# 2V5_DRS4_SUPPLY.net
KiCad netlist of a schematic drawn in Altium Designer
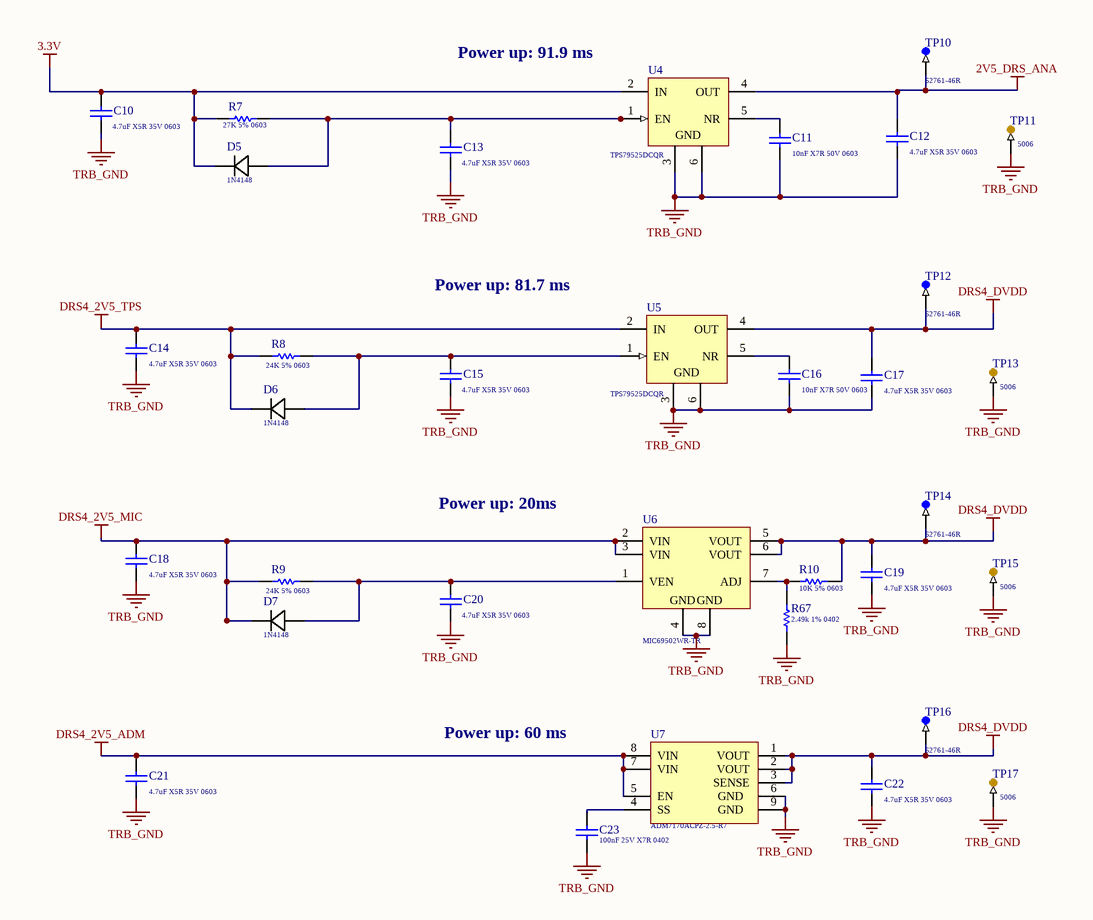
[diagram p0: 2V5_DRS4_SUPPLY.SchDoc]

(export (version "E")
  (design (tool "Eeschema 10.0.6"))
  (components
    (comp (ref "C10")
      (value "Cap_Murata_ZRB18AR6YA475ME05L_4.7uF")
      (footprint "Cap_Murata_ZRB18AR6YA475ME05L_4.7uF")
      (description "CAP CER 4.7uF 35V X5R 0603")
      (fields (field (name "CAPACITANCE") "4.7uF X5R 35V 0603"))
      (libsource (lib "Cap_Murata_ZRB18AR6YA475ME05L_4.7uF") (part "Cap_Murata_ZRB18AR6YA475ME05L_4.7uF"))
    )
    (comp (ref "C11")
      (value "Cap_Kemet_C0603C103J5RACTU_eec")
      (footprint "Kemet_C0603_0")
      (description "CAP CER 10nF 50V X7R 0603")
      (fields
        (field (name "PART NUMBER") "C0603C103J5RACTU")
        (field (name "MANUFACTURER") "Kemet")
        (field (name "CAPACITANCE") "10nF X7R 50V 0603")
      )
      (libsource (lib "Cap_Kemet_C0603C103J5RACTU_10nF") (part "Cap_Kemet_C0603C103J5RACTU_eec"))
    )
    (comp (ref "C12")
      (value "Cap_Murata_ZRB18AR6YA475ME05L_4.7uF")
      (footprint "Cap_Murata_ZRB18AR6YA475ME05L_4.7uF")
      (description "CAP CER 4.7uF 35V X5R 0603")
      (fields (field (name "CAPACITANCE") "4.7uF X5R 35V 0603"))
      (libsource (lib "Cap_Murata_ZRB18AR6YA475ME05L_4.7uF") (part "Cap_Murata_ZRB18AR6YA475ME05L_4.7uF"))
    )
    (comp (ref "C13")
      (value "Cap_Murata_ZRB18AR6YA475ME05L_4.7uF")
      (footprint "Cap_Murata_ZRB18AR6YA475ME05L_4.7uF")
      (description "CAP CER 4.7uF 35V X5R 0603")
      (fields (field (name "CAPACITANCE") "4.7uF X5R 35V 0603"))
      (libsource (lib "Cap_Murata_ZRB18AR6YA475ME05L_4.7uF") (part "Cap_Murata_ZRB18AR6YA475ME05L_4.7uF"))
    )
    (comp (ref "C14")
      (value "Cap_Murata_ZRB18AR6YA475ME05L_4.7uF")
      (footprint "Cap_Murata_ZRB18AR6YA475ME05L_4.7uF")
      (description "CAP CER 4.7uF 35V X5R 0603")
      (fields (field (name "CAPACITANCE") "4.7uF X5R 35V 0603"))
      (libsource (lib "Cap_Murata_ZRB18AR6YA475ME05L_4.7uF") (part "Cap_Murata_ZRB18AR6YA475ME05L_4.7uF"))
    )
    (comp (ref "C15")
      (value "Cap_Murata_ZRB18AR6YA475ME05L_4.7uF")
      (footprint "Cap_Murata_ZRB18AR6YA475ME05L_4.7uF")
      (description "CAP CER 4.7uF 35V X5R 0603")
      (fields (field (name "CAPACITANCE") "4.7uF X5R 35V 0603"))
      (libsource (lib "Cap_Murata_ZRB18AR6YA475ME05L_4.7uF") (part "Cap_Murata_ZRB18AR6YA475ME05L_4.7uF"))
    )
    (comp (ref "C16")
      (value "Cap_Kemet_C0603C103J5RACTU_eec")
      (footprint "Kemet_C0603_0")
      (description "CAP CER 10nF 50V X7R 0603")
      (fields
        (field (name "PART NUMBER") "C0603C103J5RACTU")
        (field (name "MANUFACTURER") "Kemet")
        (field (name "CAPACITANCE") "10nF X7R 50V 0603")
      )
      (libsource (lib "Cap_Kemet_C0603C103J5RACTU_10nF") (part "Cap_Kemet_C0603C103J5RACTU_eec"))
    )
    (comp (ref "C17")
      (value "Cap_Murata_ZRB18AR6YA475ME05L_4.7uF")
      (footprint "Cap_Murata_ZRB18AR6YA475ME05L_4.7uF")
      (description "CAP CER 4.7uF 35V X5R 0603")
      (fields (field (name "CAPACITANCE") "4.7uF X5R 35V 0603"))
      (libsource (lib "Cap_Murata_ZRB18AR6YA475ME05L_4.7uF") (part "Cap_Murata_ZRB18AR6YA475ME05L_4.7uF"))
    )
    (comp (ref "C18")
      (value "Cap_Murata_ZRB18AR6YA475ME05L_4.7uF")
      (footprint "Cap_Murata_ZRB18AR6YA475ME05L_4.7uF")
      (description "CAP CER 4.7uF 35V X5R 0603")
      (fields (field (name "CAPACITANCE") "4.7uF X5R 35V 0603"))
      (libsource (lib "Cap_Murata_ZRB18AR6YA475ME05L_4.7uF") (part "Cap_Murata_ZRB18AR6YA475ME05L_4.7uF"))
    )
    (comp (ref "C19")
      (value "Cap_Murata_ZRB18AR6YA475ME05L_4.7uF")
      (footprint "Cap_Murata_ZRB18AR6YA475ME05L_4.7uF")
      (description "CAP CER 4.7uF 35V X5R 0603")
      (fields (field (name "CAPACITANCE") "4.7uF X5R 35V 0603"))
      (libsource (lib "Cap_Murata_ZRB18AR6YA475ME05L_4.7uF") (part "Cap_Murata_ZRB18AR6YA475ME05L_4.7uF"))
    )
    (comp (ref "C20")
      (value "Cap_Murata_ZRB18AR6YA475ME05L_4.7uF")
      (footprint "Cap_Murata_ZRB18AR6YA475ME05L_4.7uF")
      (description "CAP CER 4.7uF 35V X5R 0603")
      (fields (field (name "CAPACITANCE") "4.7uF X5R 35V 0603"))
      (libsource (lib "Cap_Murata_ZRB18AR6YA475ME05L_4.7uF") (part "Cap_Murata_ZRB18AR6YA475ME05L_4.7uF"))
    )
    (comp (ref "C21")
      (value "Cap_Murata_ZRB18AR6YA475ME05L_4.7uF")
      (footprint "Cap_Murata_ZRB18AR6YA475ME05L_4.7uF")
      (description "CAP CER 4.7uF 35V X5R 0603")
      (fields (field (name "CAPACITANCE") "4.7uF X5R 35V 0603"))
      (libsource (lib "Cap_Murata_ZRB18AR6YA475ME05L_4.7uF") (part "Cap_Murata_ZRB18AR6YA475ME05L_4.7uF"))
    )
    (comp (ref "C22")
      (value "Cap_Murata_ZRB18AR6YA475ME05L_4.7uF")
      (footprint "Cap_Murata_ZRB18AR6YA475ME05L_4.7uF")
      (description "CAP CER 4.7uF 35V X5R 0603")
      (fields (field (name "CAPACITANCE") "4.7uF X5R 35V 0603"))
      (libsource (lib "Cap_Murata_ZRB18AR6YA475ME05L_4.7uF") (part "Cap_Murata_ZRB18AR6YA475ME05L_4.7uF"))
    )
    (comp (ref "C23")
      (value "Cap_Taiyo_Yuden_TMK105B7104KV-FR_100nF")
      (footprint "Cap_Taiyo_Yuden_TMK105B7104KV-FR_100nF")
      (description "CAP CER 100nF 25V X7R 0402")
      (fields (field (name "CAPACITANCE") "100nF 25V X7R 0402"))
      (libsource (lib "Cap_Taiyo_Yuden_TMK105B7104KV-FR_100nF") (part "Cap_Taiyo_Yuden_TMK105B7104KV-FR_100nF"))
    )
    (comp (ref "D5")
      (value "Diode_ON_Semiconductor_1N4148WT_300mA")
      (footprint "Diode_ON_Semiconductor_1N4148WT_300mA")
      (description "Diodes - General Purpose, Power, Switching SINGLE JUNC. 75V 4.0NS COMP")
      (fields (field (name "SERIES") "1N4148"))
      (libsource (lib "Diode_ON_Semiconductor_1N4148WT_300mA") (part "Diode_ON_Semiconductor_1N4148WT_300mA"))
    )
    (comp (ref "D6")
      (value "Diode_ON_Semiconductor_1N4148WT_300mA")
      (footprint "Diode_ON_Semiconductor_1N4148WT_300mA")
      (description "Diodes - General Purpose, Power, Switching SINGLE JUNC. 75V 4.0NS COMP")
      (fields (field (name "SERIES") "1N4148"))
      (libsource (lib "Diode_ON_Semiconductor_1N4148WT_300mA") (part "Diode_ON_Semiconductor_1N4148WT_300mA"))
    )
    (comp (ref "D7")
      (value "Diode_ON_Semiconductor_1N4148WT_300mA")
      (footprint "Diode_ON_Semiconductor_1N4148WT_300mA")
      (description "Diodes - General Purpose, Power, Switching SINGLE JUNC. 75V 4.0NS COMP")
      (fields (field (name "SERIES") "1N4148"))
      (libsource (lib "Diode_ON_Semiconductor_1N4148WT_300mA") (part "Diode_ON_Semiconductor_1N4148WT_300mA"))
    )
    (comp (ref "R7")
      (value "27K 5% 0603")
      (footprint "RESC0603(1608)_L")
      (description "27K 0.1W 5% 0603 (1608 Metric)  SMD")
      (fields (field (name "POWER") "0.1 W") (field (name "TOLERANCE") "5 %"))
      (libsource (lib "Altium Content Vault") (part "RES"))
    )
    (comp (ref "R8")
      (value "24K 5% 0603")
      (footprint "RESC0603(1608)_L")
      (description "24K 0.1W 5% 0603 (1608 Metric)  SMD")
      (fields (field (name "TOLERANCE") "5 %") (field (name "POWER") "0.1 W"))
      (libsource (lib "Altium Content Vault") (part "RES"))
    )
    (comp (ref "R9")
      (value "24K 5% 0603")
      (footprint "RESC0603(1608)_L")
      (description "24K 0.1W 5% 0603 (1608 Metric)  SMD")
      (fields (field (name "TOLERANCE") "5 %") (field (name "POWER") "0.1 W"))
      (libsource (lib "Altium Content Vault") (part "RES"))
    )
    (comp (ref "R10")
      (value "10K 5% 0603")
      (footprint "RESC0603(1608)_L")
      (description "10K 0.1W 5% 0603 (1608 Metric)  SMD")
      (fields (field (name "TOLERANCE") "5 %") (field (name "POWER") "0.1 W"))
      (libsource (lib "Altium Content Vault") (part "RES"))
    )
    (comp (ref "R67")
      (value "Res_Yageo_RC0402FR-132K49L_2.48kOhm")
      (footprint "Res_Yageo_RC0402FR-132K49L_2.48kOhm")
      (description "Thick Film Resistors - SMD 2.49K ohm 1% 50V General Purpose")
      (fields (field (name "RESISTANCE") "2.49k 1% 0402"))
      (libsource (lib "Res_Yageo_RC0402FR-132K49L_2.48kOhm") (part "Res_Yageo_RC0402FR-132K49L_2.48kOhm"))
    )
    (comp (ref "TP10")
      (value "TP_Harwin_S2761_46R")
      (footprint "TP_Harwin_S2761_46R")
      (description "Circuit Board Hardware - PCB SMT Mini Test Terminal, Reel")
      (fields (field (name "SERIES") "S2761-46R"))
      (libsource (lib "TP_Harwin_S2761_46R") (part "TP_Harwin_S2761_46R"))
    )
    (comp (ref "TP11")
      (value "TP_Keystone_Electronics_5006")
      (footprint "TP_Keystone_Electronics_5006")
      (description "Circuit Board Hardware - PCB TEST POINT BLK .063")
      (fields (field (name "SERIES") "5006"))
      (libsource (lib "TP_Keystone_Electronics_5006") (part "TP_Keystone_Electronics_5006"))
    )
    (comp (ref "TP12")
      (value "TP_Harwin_S2761_46R")
      (footprint "TP_Harwin_S2761_46R")
      (description "Circuit Board Hardware - PCB SMT Mini Test Terminal, Reel")
      (fields (field (name "SERIES") "S2761-46R"))
      (libsource (lib "TP_Harwin_S2761_46R") (part "TP_Harwin_S2761_46R"))
    )
    (comp (ref "TP13")
      (value "TP_Keystone_Electronics_5006")
      (footprint "TP_Keystone_Electronics_5006")
      (description "Circuit Board Hardware - PCB TEST POINT BLK .063")
      (fields (field (name "SERIES") "5006"))
      (libsource (lib "TP_Keystone_Electronics_5006") (part "TP_Keystone_Electronics_5006"))
    )
    (comp (ref "TP14")
      (value "TP_Harwin_S2761_46R")
      (footprint "TP_Harwin_S2761_46R")
      (description "Circuit Board Hardware - PCB SMT Mini Test Terminal, Reel")
      (fields (field (name "SERIES") "S2761-46R"))
      (libsource (lib "TP_Harwin_S2761_46R") (part "TP_Harwin_S2761_46R"))
    )
    (comp (ref "TP15")
      (value "TP_Keystone_Electronics_5006")
      (footprint "TP_Keystone_Electronics_5006")
      (description "Circuit Board Hardware - PCB TEST POINT BLK .063")
      (fields (field (name "SERIES") "5006"))
      (libsource (lib "TP_Keystone_Electronics_5006") (part "TP_Keystone_Electronics_5006"))
    )
    (comp (ref "TP16")
      (value "TP_Harwin_S2761_46R")
      (footprint "TP_Harwin_S2761_46R")
      (description "Circuit Board Hardware - PCB SMT Mini Test Terminal, Reel")
      (fields (field (name "SERIES") "S2761-46R"))
      (libsource (lib "TP_Harwin_S2761_46R") (part "TP_Harwin_S2761_46R"))
    )
    (comp (ref "TP17")
      (value "TP_Keystone_Electronics_5006")
      (footprint "TP_Keystone_Electronics_5006")
      (description "Circuit Board Hardware - PCB TEST POINT BLK .063")
      (fields (field (name "SERIES") "5006"))
      (libsource (lib "TP_Keystone_Electronics_5006") (part "TP_Keystone_Electronics_5006"))
    )
    (comp (ref "U4")
      (value "TPS79525DCQR")
      (footprint "DCQ0006A_N")
      (fields (field (name "MANUFACTURER") "Texas Instruments"))
      (libsource (lib "IC_Texas Instruments_TPS79525DCQR") (part "TPS79525DCQR"))
    )
    (comp (ref "U5")
      (value "TPS79525DCQR")
      (footprint "DCQ0006A_N")
      (fields (field (name "MANUFACTURER") "Texas Instruments"))
      (libsource (lib "IC_Texas Instruments_TPS79525DCQR") (part "TPS79525DCQR"))
    )
    (comp (ref "U6")
      (value "LDO_Microchip_MIC69502WR-TR_ADJ")
      (footprint "LDO_Microchip_MIC69502WR-TR_ADJ")
      (description "LDO Voltage Regulators 5A Low VIN LDO Regulator with 0.5Vref")
      (fields (field (name "SERIES") "MIC69502WR-TR"))
      (libsource (lib "LDO_Microchip_MIC69502WR-TR_ADJ") (part "LDO_Microchip_MIC69502WR-TR_ADJ"))
    )
    (comp (ref "U7")
      (value "LDO_Analog_Devices_ADM7170ACPZ-2.5-R7_2.5V")
      (footprint "LDO_Analog_Devices_ADM7170ACPZ-2.5-R7_2.5V")
      (description "LDO Voltage Regulators 0.5A Hi PSRR FT LDO 2.5V")
      (fields (field (name "SERIES") "ADM7170ACPZ-2.5-R7"))
      (libsource (lib "LDO_Analog_Devices_ADM7170ACPZ-2.5-R7_2.5V") (part "LDO_Analog_Devices_ADM7170ACPZ-2.5-R7_2.5V"))
    )
  )
  (nets
    (net (code "1") (name "2V5_DRS_ANA") (class "Default")
      (node (ref "C12") (pin "2") (pinfunction "2_2") (pintype "passive"))
      (node (ref "TP10") (pin "1") (pinfunction "1_1") (pintype "input"))
      (node (ref "U4") (pin "4") (pinfunction "OUT_4") (pintype "power_in"))
    )
    (net (code "2") (name "3.3V") (class "Default")
      (node (ref "C10") (pin "2") (pinfunction "2_2") (pintype "passive"))
      (node (ref "D5") (pin "1") (pinfunction "1_1") (pintype "passive"))
      (node (ref "R7") (pin "1") (pinfunction "1_1") (pintype "passive"))
      (node (ref "U4") (pin "2") (pinfunction "IN_2") (pintype "power_in"))
    )
    (net (code "3") (name "DRS4_2V5_ADM") (class "Default")
      (node (ref "C21") (pin "2") (pinfunction "2_2") (pintype "passive"))
      (node (ref "U7") (pin "5") (pinfunction "EN_5") (pintype "power_in"))
      (node (ref "U7") (pin "7") (pinfunction "VIN_7") (pintype "power_in"))
      (node (ref "U7") (pin "8") (pinfunction "VIN_8") (pintype "power_in"))
    )
    (net (code "4") (name "DRS4_2V5_MIC") (class "Default")
      (node (ref "C18") (pin "2") (pinfunction "2_2") (pintype "passive"))
      (node (ref "D7") (pin "1") (pinfunction "1_1") (pintype "passive"))
      (node (ref "R9") (pin "1") (pinfunction "1_1") (pintype "passive"))
      (node (ref "U6") (pin "2") (pinfunction "VIN_2") (pintype "power_in"))
      (node (ref "U6") (pin "3") (pinfunction "VIN_3") (pintype "power_in"))
    )
    (net (code "5") (name "DRS4_2V5_TPS") (class "Default")
      (node (ref "C14") (pin "2") (pinfunction "2_2") (pintype "passive"))
      (node (ref "D6") (pin "1") (pinfunction "1_1") (pintype "passive"))
      (node (ref "R8") (pin "1") (pinfunction "1_1") (pintype "passive"))
      (node (ref "U5") (pin "2") (pinfunction "IN_2") (pintype "power_in"))
    )
    (net (code "6") (name "DRS4_DVDD") (class "Default")
      (node (ref "C17") (pin "2") (pinfunction "2_2") (pintype "passive"))
      (node (ref "C19") (pin "2") (pinfunction "2_2") (pintype "passive"))
      (node (ref "C22") (pin "2") (pinfunction "2_2") (pintype "passive"))
      (node (ref "R10") (pin "2") (pinfunction "2_2") (pintype "passive"))
      (node (ref "TP12") (pin "1") (pinfunction "1_1") (pintype "input"))
      (node (ref "TP14") (pin "1") (pinfunction "1_1") (pintype "input"))
      (node (ref "TP16") (pin "1") (pinfunction "1_1") (pintype "input"))
      (node (ref "U5") (pin "4") (pinfunction "OUT_4") (pintype "power_in"))
      (node (ref "U6") (pin "5") (pinfunction "VOUT_5") (pintype "power_in"))
      (node (ref "U6") (pin "6") (pinfunction "VOUT_6") (pintype "power_in"))
      (node (ref "U7") (pin "1") (pinfunction "VOUT_1") (pintype "power_in"))
      (node (ref "U7") (pin "2") (pinfunction "VOUT_2") (pintype "power_in"))
      (node (ref "U7") (pin "3") (pinfunction "SENSE_3") (pintype "power_in"))
    )
    (net (code "7") (name "Net-(U4-EN)") (class "Default")
      (node (ref "C13") (pin "2") (pinfunction "2_2") (pintype "passive"))
      (node (ref "D5") (pin "2") (pinfunction "2_2") (pintype "passive"))
      (node (ref "R7") (pin "2") (pinfunction "2_2") (pintype "passive"))
      (node (ref "U4") (pin "1") (pinfunction "EN_1") (pintype "input"))
    )
    (net (code "8") (name "Net-(U4-NR)") (class "Default")
      (node (ref "C11") (pin "1") (pinfunction "1_1") (pintype "passive"))
      (node (ref "U4") (pin "5") (pinfunction "NR_5") (pintype "passive"))
    )
    (net (code "9") (name "Net-(U5-EN)") (class "Default")
      (node (ref "C15") (pin "2") (pinfunction "2_2") (pintype "passive"))
      (node (ref "D6") (pin "2") (pinfunction "2_2") (pintype "passive"))
      (node (ref "R8") (pin "2") (pinfunction "2_2") (pintype "passive"))
      (node (ref "U5") (pin "1") (pinfunction "EN_1") (pintype "input"))
    )
    (net (code "10") (name "Net-(U5-NR)") (class "Default")
      (node (ref "C16") (pin "1") (pinfunction "1_1") (pintype "passive"))
      (node (ref "U5") (pin "5") (pinfunction "NR_5") (pintype "passive"))
    )
    (net (code "11") (name "Net-(U6-ADJ)") (class "Default")
      (node (ref "R10") (pin "1") (pinfunction "1_1") (pintype "passive"))
      (node (ref "R67") (pin "2") (pinfunction "2_2") (pintype "passive"))
      (node (ref "U6") (pin "7") (pinfunction "ADJ_7") (pintype "power_in"))
    )
    (net (code "12") (name "Net-(U6-VEN)") (class "Default")
      (node (ref "C20") (pin "2") (pinfunction "2_2") (pintype "passive"))
      (node (ref "D7") (pin "2") (pinfunction "2_2") (pintype "passive"))
      (node (ref "R9") (pin "2") (pinfunction "2_2") (pintype "passive"))
      (node (ref "U6") (pin "1") (pinfunction "VEN_1") (pintype "power_in"))
    )
    (net (code "13") (name "Net-(U7-SS)") (class "Default")
      (node (ref "C23") (pin "2") (pinfunction "2_2") (pintype "passive"))
      (node (ref "U7") (pin "4") (pinfunction "SS_4") (pintype "power_in"))
    )
    (net (code "14") (name "TRB_GND") (class "Default")
      (node (ref "C10") (pin "1") (pinfunction "1_1") (pintype "passive"))
      (node (ref "C11") (pin "2") (pinfunction "2_2") (pintype "passive"))
      (node (ref "C12") (pin "1") (pinfunction "1_1") (pintype "passive"))
      (node (ref "C13") (pin "1") (pinfunction "1_1") (pintype "passive"))
      (node (ref "C14") (pin "1") (pinfunction "1_1") (pintype "passive"))
      (node (ref "C15") (pin "1") (pinfunction "1_1") (pintype "passive"))
      (node (ref "C16") (pin "2") (pinfunction "2_2") (pintype "passive"))
      (node (ref "C17") (pin "1") (pinfunction "1_1") (pintype "passive"))
      (node (ref "C18") (pin "1") (pinfunction "1_1") (pintype "passive"))
      (node (ref "C19") (pin "1") (pinfunction "1_1") (pintype "passive"))
      (node (ref "C20") (pin "1") (pinfunction "1_1") (pintype "passive"))
      (node (ref "C21") (pin "1") (pinfunction "1_1") (pintype "passive"))
      (node (ref "C22") (pin "1") (pinfunction "1_1") (pintype "passive"))
      (node (ref "C23") (pin "1") (pinfunction "1_1") (pintype "passive"))
      (node (ref "R67") (pin "1") (pinfunction "1_1") (pintype "passive"))
      (node (ref "TP11") (pin "1") (pinfunction "1_1") (pintype "input"))
      (node (ref "TP13") (pin "1") (pinfunction "1_1") (pintype "input"))
      (node (ref "TP15") (pin "1") (pinfunction "1_1") (pintype "input"))
      (node (ref "TP17") (pin "1") (pinfunction "1_1") (pintype "input"))
      (node (ref "U4") (pin "3") (pinfunction "GND_3") (pintype "power_in"))
      (node (ref "U4") (pin "6") (pinfunction "GND_6") (pintype "power_in"))
      (node (ref "U5") (pin "3") (pinfunction "GND_3") (pintype "power_in"))
      (node (ref "U5") (pin "6") (pinfunction "GND_6") (pintype "power_in"))
      (node (ref "U6") (pin "4") (pinfunction "GND_4") (pintype "power_in"))
      (node (ref "U6") (pin "8") (pinfunction "GND_8") (pintype "power_in"))
      (node (ref "U7") (pin "6") (pinfunction "GND_6") (pintype "power_in"))
      (node (ref "U7") (pin "9") (pinfunction "GND_9") (pintype "power_in"))
    )
  )
)
